# dasblinkenhat-controller-mk-2_1.net
KiCad netlist of a schematic drawn in EAGLE
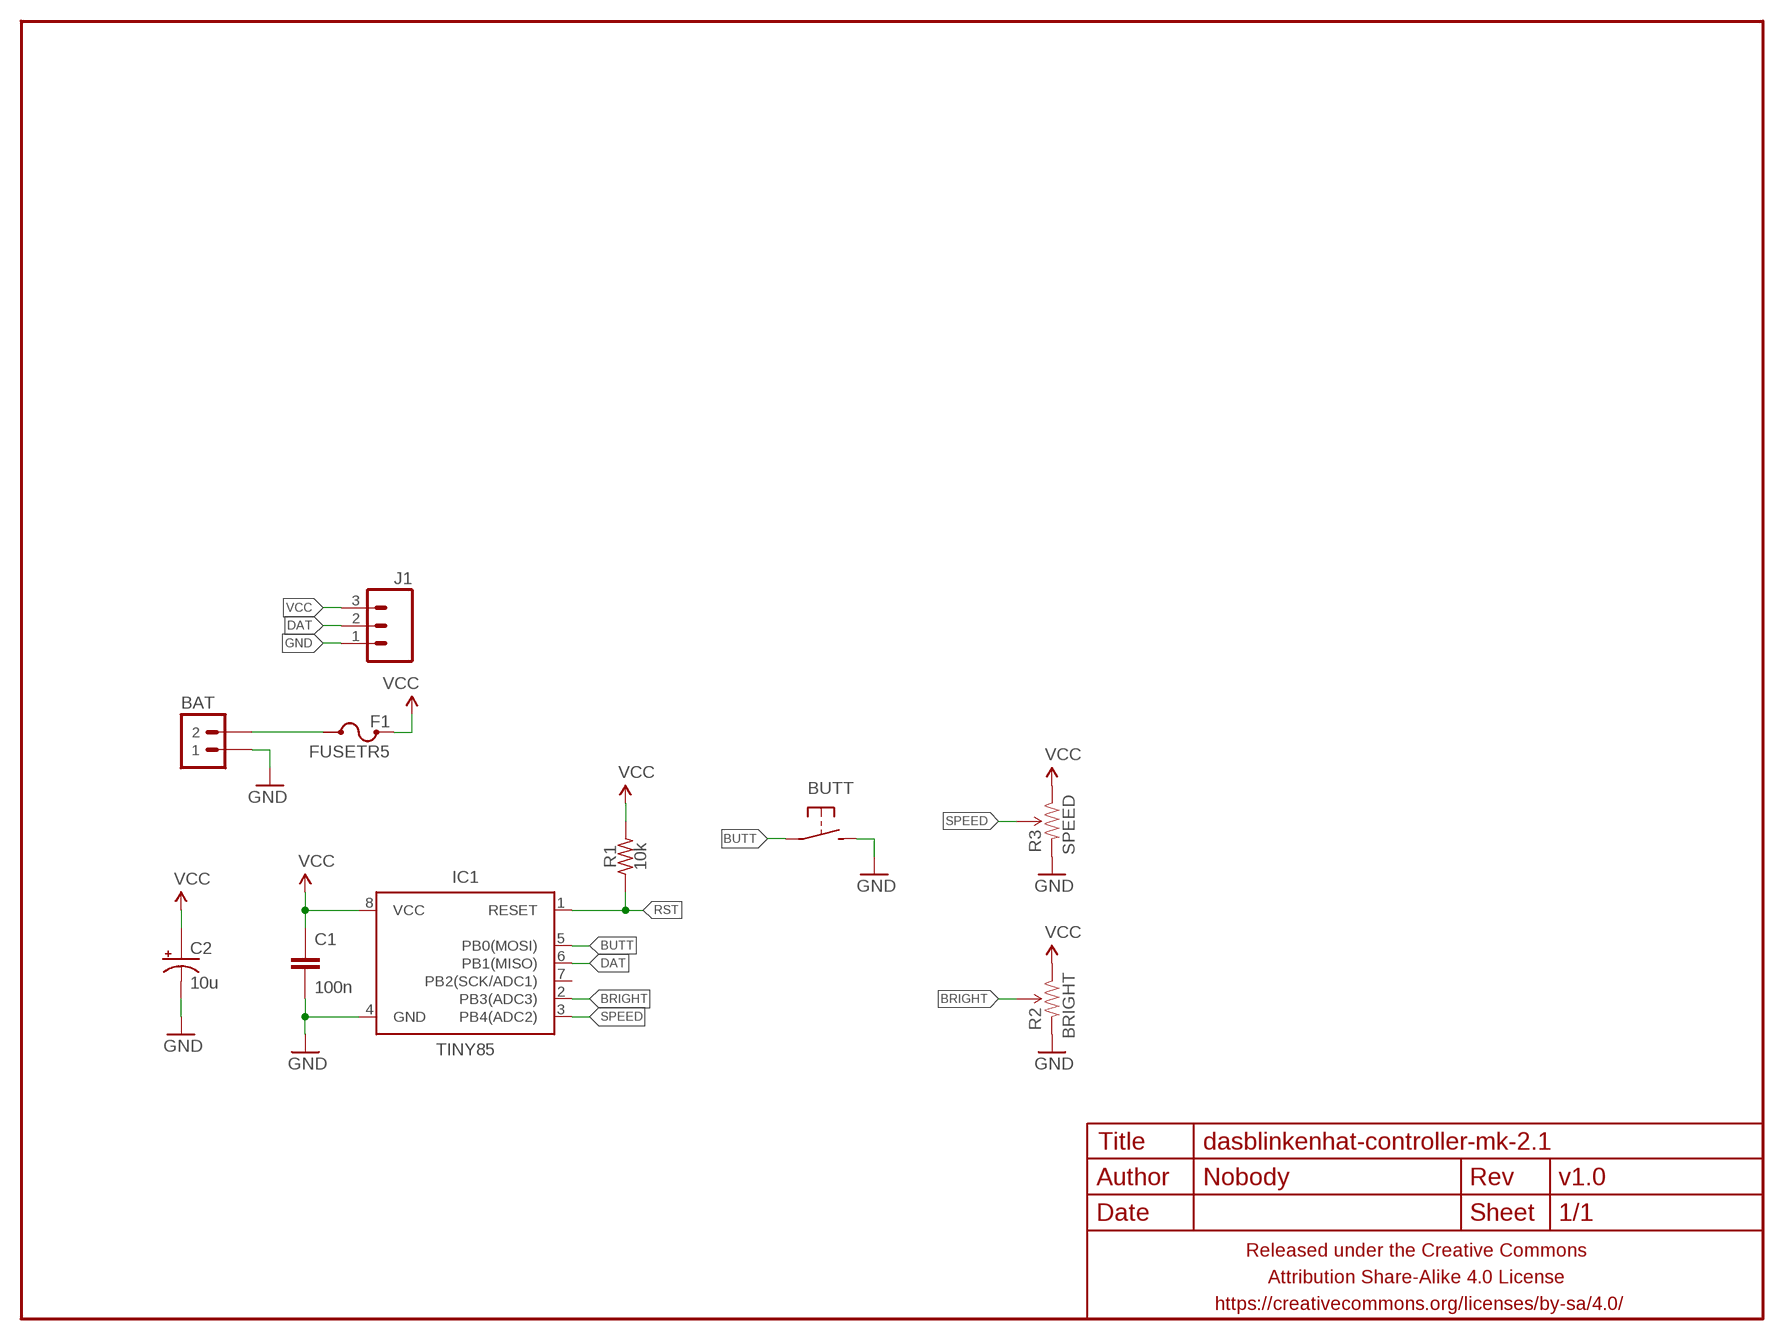
[diagram p0: schematic, sheet 1]

(export (version "E")
  (design (tool "Eeschema 10.0.6"))
  (components
    (comp (ref "BAT")
      (value "M02JST-PTH-RA-R+")
      (footprint "eagle-import:JST-2-PH-RA-PTH-R+")
      (libsource (lib "eagle-import") (part "M02JST-PTH-RA-R+"))
    )
    (comp (ref "BUTT")
      (value "DTS-6MM")
      (footprint "eagle-import:DTS-6-SMALL-PADS")
      (libsource (lib "eagle-import") (part "SPST-NO-TACT6MM-PTH-SMALL-PADS"))
    )
    (comp (ref "C1")
      (value "100n")
      (footprint "eagle-import:C025-024X044")
      (libsource (lib "eagle-import") (part "CAPACITOR-CERAMIC025-024X044"))
    )
    (comp (ref "C2")
      (value "10u")
      (footprint "eagle-import:E2-5")
      (libsource (lib "eagle-import") (part "CAPACITOR-POLARIZEDE2-5"))
    )
    (comp (ref "F1")
      (value "FUSETR5")
      (footprint "eagle-import:TR5")
      (libsource (lib "eagle-import") (part "FUSETR5"))
    )
    (comp (ref "FRAME1")
      (value "FRAME-LETTERNO_PACKAGE")
      (footprint "eagle-import:DUMMY")
      (fields (field (name "VERSION") "v1.0") (field (name "DESIGNER") "Nobody"))
      (libsource (lib "eagle-import") (part "FRAME-LETTERNO_PACKAGE"))
    )
    (comp (ref "IC1")
      (value "TINY85")
      (footprint "eagle-import:DIP08")
      (libsource (lib "eagle-import") (part "ATTINY45TINY85-20-DIP"))
    )
    (comp (ref "J1")
      (value "M03JST-XH-RA-PTH")
      (footprint "eagle-import:JST-3-XH-RA-PTH")
      (libsource (lib "eagle-import") (part "M03JST-XH-RA-PTH"))
    )
    (comp (ref "R1")
      (value "10k")
      (footprint "eagle-import:RESISTOR-AXIAL-PTH-5.08MM")
      (libsource (lib "eagle-import") (part "RESISTORPTH-AXIAL-5.08MM"))
    )
    (comp (ref "R2")
      (value "BRIGHT")
      (footprint "eagle-import:TRIM_POT_PTH2")
      (libsource (lib "eagle-import") (part "TRIMPOTPTH2"))
    )
    (comp (ref "R3")
      (value "SPEED")
      (footprint "eagle-import:TRIM_POT_PTH2")
      (libsource (lib "eagle-import") (part "TRIMPOTPTH2"))
    )
  )
  (nets
    (net (code "1") (name "BRIGHT") (class "Default")
      (node (ref "IC1") (pin "2") (pinfunction "PB3(ADC3)_2") (pintype "bidirectional"))
      (node (ref "R2") (pin "2") (pinfunction "WIPER_2") (pintype "passive"))
    )
    (net (code "2") (name "BUTT") (class "Default")
      (node (ref "BUTT") (pin "1") (pinfunction "1_1") (pintype "passive"))
      (node (ref "BUTT") (pin "2") (pinfunction "1_2") (pintype "passive"))
      (node (ref "IC1") (pin "5") (pinfunction "PB0(MOSI)_5") (pintype "bidirectional"))
    )
    (net (code "3") (name "DAT") (class "Default")
      (node (ref "IC1") (pin "6") (pinfunction "PB1(MISO)_6") (pintype "bidirectional"))
      (node (ref "J1") (pin "2") (pinfunction "2_2") (pintype "passive"))
    )
    (net (code "4") (name "GND") (class "Default")
      (node (ref "BAT") (pin "1") (pinfunction "1_1") (pintype "passive"))
      (node (ref "BUTT") (pin "3") (pinfunction "2_3") (pintype "passive"))
      (node (ref "BUTT") (pin "4") (pinfunction "2_4") (pintype "passive"))
      (node (ref "C1") (pin "2") (pinfunction "2_2") (pintype "passive"))
      (node (ref "C2") (pin "-") (pinfunction "-_-") (pintype "passive"))
      (node (ref "IC1") (pin "4") (pinfunction "GND_4") (pintype "bidirectional"))
      (node (ref "J1") (pin "1") (pinfunction "1_1") (pintype "passive"))
      (node (ref "R2") (pin "3") (pinfunction "CW_3") (pintype "passive"))
      (node (ref "R3") (pin "3") (pinfunction "CW_3") (pintype "passive"))
    )
    (net (code "5") (name "Net-(BAT-Pad2)") (class "Default")
      (node (ref "BAT") (pin "2") (pinfunction "2_2") (pintype "passive"))
      (node (ref "F1") (pin "2") (pinfunction "2_2") (pintype "passive"))
    )
    (net (code "6") (name "RST") (class "Default")
      (node (ref "IC1") (pin "1") (pinfunction "RESET_1") (pintype "bidirectional"))
      (node (ref "R1") (pin "P$1") (pinfunction "1_P$1") (pintype "passive"))
    )
    (net (code "7") (name "SPEED") (class "Default")
      (node (ref "IC1") (pin "3") (pinfunction "PB4(ADC2)_3") (pintype "bidirectional"))
      (node (ref "R3") (pin "2") (pinfunction "WIPER_2") (pintype "passive"))
    )
    (net (code "8") (name "VCC") (class "Default")
      (node (ref "C1") (pin "1") (pinfunction "1_1") (pintype "passive"))
      (node (ref "C2") (pin "+") (pinfunction "+_+") (pintype "passive"))
      (node (ref "F1") (pin "1") (pinfunction "1_1") (pintype "passive"))
      (node (ref "IC1") (pin "8") (pinfunction "VCC_8") (pintype "bidirectional"))
      (node (ref "J1") (pin "3") (pinfunction "3_3") (pintype "passive"))
      (node (ref "R1") (pin "P$2") (pinfunction "2_P$2") (pintype "passive"))
      (node (ref "R2") (pin "1") (pinfunction "CCW_1") (pintype "passive"))
      (node (ref "R3") (pin "1") (pinfunction "CCW_1") (pintype "passive"))
    )
    (net (code "9") (name "unconnected-(IC1-PB2(SCK{slash}ADC1)-Pad7)") (class "Default")
      (node (ref "IC1") (pin "7") (pinfunction "PB2(SCK/ADC1)_7") (pintype "bidirectional"))
    )
  )
)
